# WizFi210_Breakout_Board.net
KiCad netlist of a schematic drawn in EAGLE
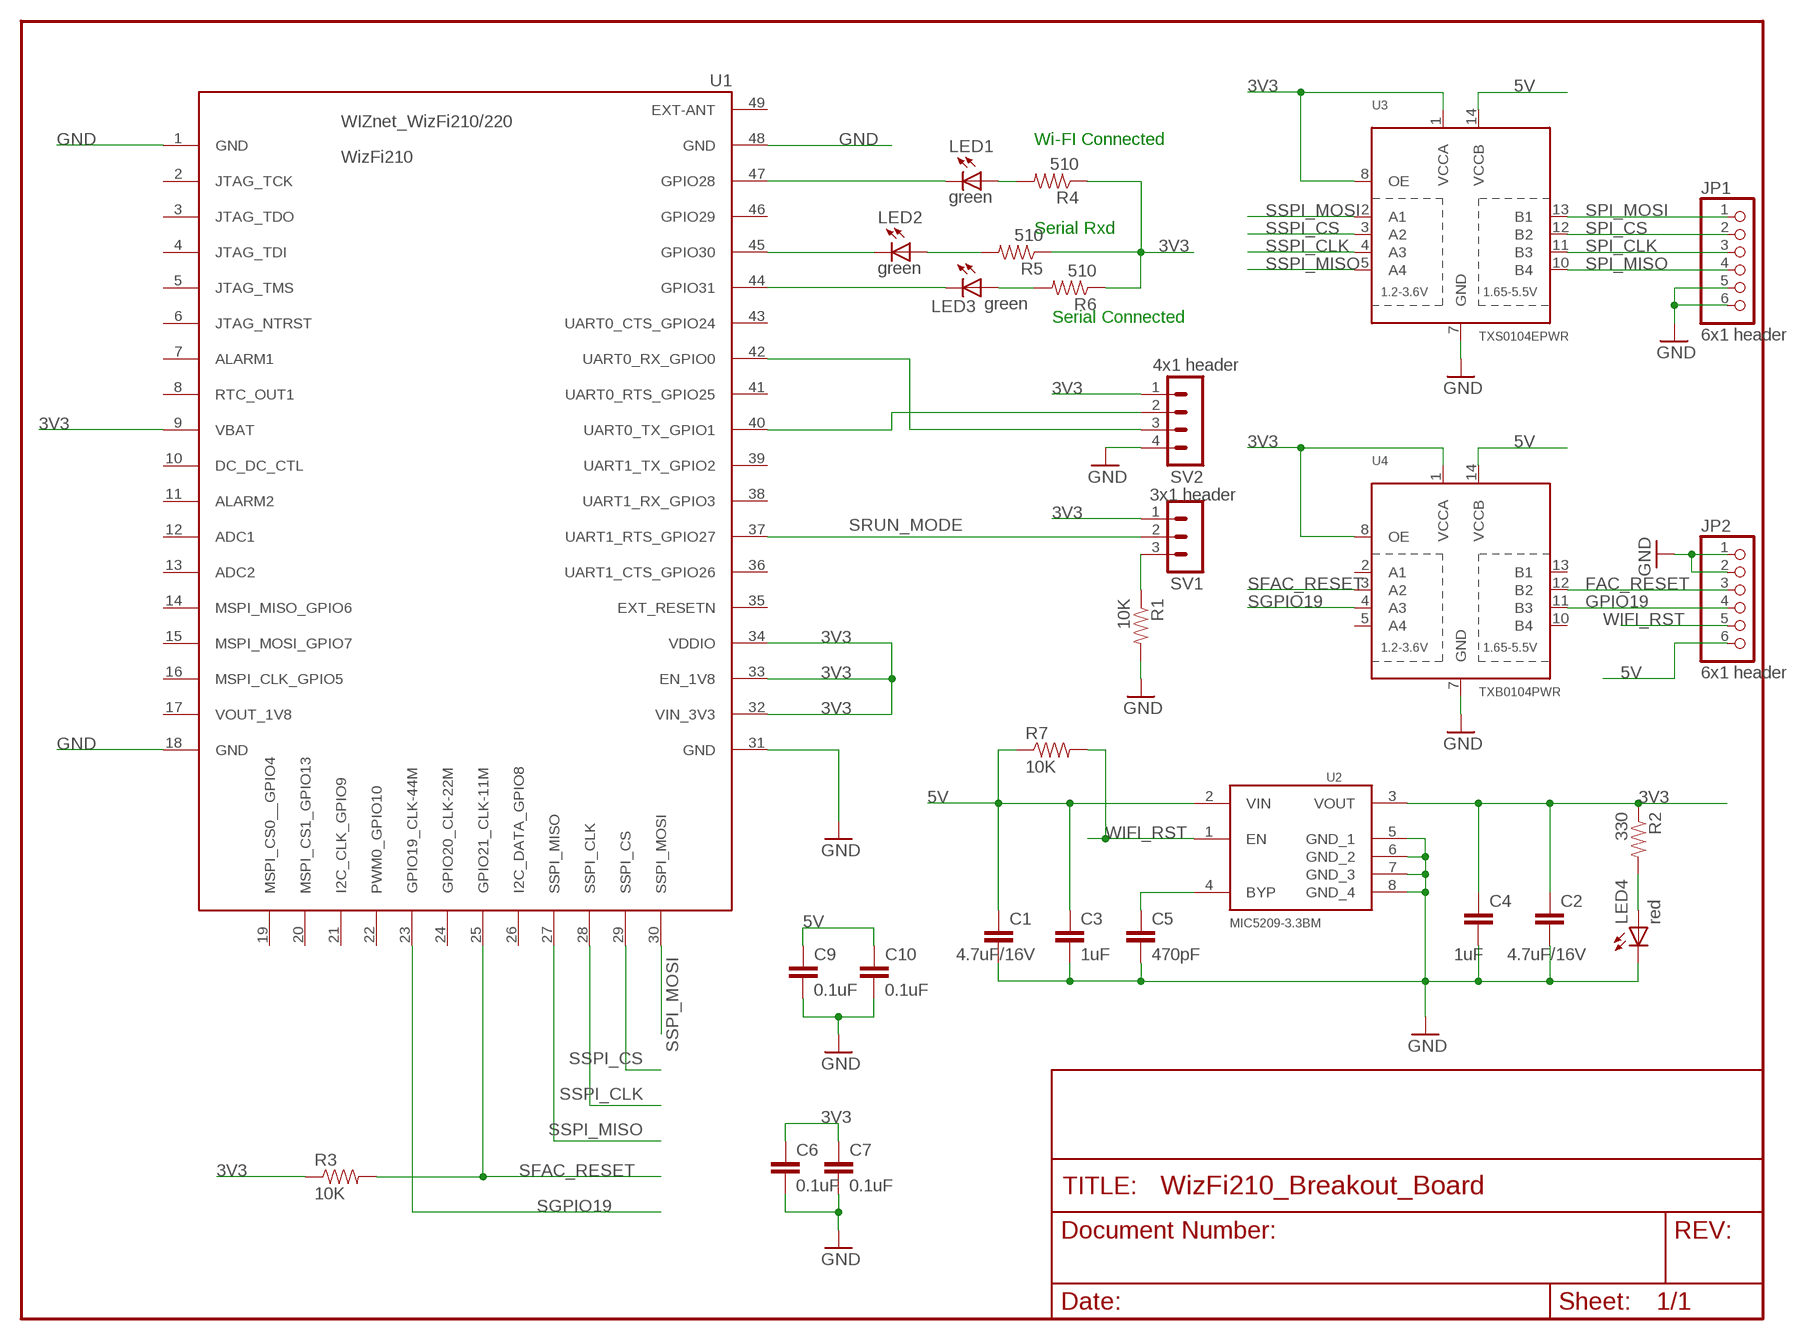
[diagram p0: schematic, sheet 1]

(export (version "E")
  (design (tool "Eeschema 10.0.6"))
  (components
    (comp (ref "C1")
      (value "4.7uF/16V")
      (footprint "eagle-import:C0805")
      (libsource (lib "eagle-import") (part "C-EUC0805"))
    )
    (comp (ref "C2")
      (value "4.7uF/16V")
      (footprint "eagle-import:C0603")
      (libsource (lib "eagle-import") (part "C-EUC0603"))
    )
    (comp (ref "C3")
      (value "1uF")
      (footprint "eagle-import:C0603")
      (libsource (lib "eagle-import") (part "C-EUC0603"))
    )
    (comp (ref "C4")
      (value "1uF")
      (footprint "eagle-import:C0805")
      (libsource (lib "eagle-import") (part "C-EUC0805"))
    )
    (comp (ref "C5")
      (value "470pF")
      (footprint "eagle-import:C0603")
      (libsource (lib "eagle-import") (part "C-EUC0603"))
    )
    (comp (ref "C6")
      (value "0.1uF")
      (footprint "eagle-import:C0603")
      (libsource (lib "eagle-import") (part "C-EUC0603"))
    )
    (comp (ref "C7")
      (value "0.1uF")
      (footprint "eagle-import:C0603")
      (libsource (lib "eagle-import") (part "C-EUC0603"))
    )
    (comp (ref "C9")
      (value "0.1uF")
      (footprint "eagle-import:C0603")
      (libsource (lib "eagle-import") (part "C-EUC0603"))
    )
    (comp (ref "C10")
      (value "0.1uF")
      (footprint "eagle-import:C0603")
      (libsource (lib "eagle-import") (part "C-EUC0603"))
    )
    (comp (ref "JP1")
      (value "6x1 header")
      (footprint "eagle-import:1X06")
      (libsource (lib "eagle-import") (part "PINHD-1X6"))
    )
    (comp (ref "JP2")
      (value "6x1 header")
      (footprint "eagle-import:1X06")
      (libsource (lib "eagle-import") (part "PINHD-1X6"))
    )
    (comp (ref "LED1")
      (value "green")
      (footprint "eagle-import:CHIP-LED0805")
      (libsource (lib "eagle-import") (part "LEDCHIP-LED0805"))
    )
    (comp (ref "LED2")
      (value "green")
      (footprint "eagle-import:CHIP-LED0805")
      (libsource (lib "eagle-import") (part "LEDCHIP-LED0805"))
    )
    (comp (ref "LED3")
      (value "green")
      (footprint "eagle-import:CHIP-LED0805")
      (libsource (lib "eagle-import") (part "LEDCHIP-LED0805"))
    )
    (comp (ref "LED4")
      (value "red")
      (footprint "eagle-import:CHIP-LED0805")
      (libsource (lib "eagle-import") (part "LEDCHIP-LED0805"))
    )
    (comp (ref "R1")
      (value "10K")
      (footprint "eagle-import:0603-RES")
      (libsource (lib "eagle-import") (part "RESISTOR0603-RES"))
    )
    (comp (ref "R2")
      (value "330")
      (footprint "eagle-import:0603-RES")
      (libsource (lib "eagle-import") (part "RESISTOR0603-RES"))
    )
    (comp (ref "R3")
      (value "10K")
      (footprint "eagle-import:0603-RES")
      (libsource (lib "eagle-import") (part "RESISTOR0603-RES"))
    )
    (comp (ref "R4")
      (value "510")
      (footprint "eagle-import:0603-RES")
      (libsource (lib "eagle-import") (part "RESISTOR0603-RES"))
    )
    (comp (ref "R5")
      (value "510")
      (footprint "eagle-import:0603-RES")
      (libsource (lib "eagle-import") (part "RESISTOR0603-RES"))
    )
    (comp (ref "R6")
      (value "510")
      (footprint "eagle-import:0603-RES")
      (libsource (lib "eagle-import") (part "RESISTOR0603-RES"))
    )
    (comp (ref "R7")
      (value "10K")
      (footprint "eagle-import:0603-RES")
      (libsource (lib "eagle-import") (part "RESISTOR0603-RES"))
    )
    (comp (ref "SV1")
      (value "3x1 header")
      (footprint "eagle-import:MA03-1")
      (libsource (lib "eagle-import") (part "MA03-1"))
    )
    (comp (ref "SV2")
      (value "4x1 header")
      (footprint "eagle-import:MA04-1")
      (libsource (lib "eagle-import") (part "MA04-1"))
    )
    (comp (ref "U1")
      (value "WizFi210")
      (footprint "eagle-import:WIZFI210_220")
      (libsource (lib "eagle-import") (part "WIZFI210/220"))
    )
    (comp (ref "U2")
      (value "MIC5209-3.3BM")
      (footprint "eagle-import:SO08")
      (libsource (lib "eagle-import") (part "MIC5209"))
    )
    (comp (ref "U3")
      (value "TXS0104EPWR")
      (footprint "eagle-import:TSSOP14")
      (libsource (lib "eagle-import") (part "TXB0104PWR"))
    )
    (comp (ref "U4")
      (value "TXB0104PWR")
      (footprint "eagle-import:TSSOP14")
      (libsource (lib "eagle-import") (part "TXB0104PWR"))
    )
  )
  (nets
    (net (code "1") (name "/3V3") (class "Default")
      (node (ref "C2") (pin "1") (pinfunction "1_1") (pintype "passive"))
      (node (ref "C4") (pin "1") (pinfunction "1_1") (pintype "passive"))
      (node (ref "C6") (pin "1") (pinfunction "1_1") (pintype "passive"))
      (node (ref "C7") (pin "1") (pinfunction "1_1") (pintype "passive"))
      (node (ref "R2") (pin "1") (pinfunction "1_1") (pintype "passive"))
      (node (ref "R3") (pin "1") (pinfunction "1_1") (pintype "passive"))
      (node (ref "R4") (pin "1") (pinfunction "1_1") (pintype "passive"))
      (node (ref "R5") (pin "1") (pinfunction "1_1") (pintype "passive"))
      (node (ref "R6") (pin "1") (pinfunction "1_1") (pintype "passive"))
      (node (ref "SV1") (pin "1") (pinfunction "1_1") (pintype "passive"))
      (node (ref "SV2") (pin "1") (pinfunction "1_1") (pintype "passive"))
      (node (ref "U1") (pin "32") (pinfunction "VIN_3V3_32") (pintype "power_in"))
      (node (ref "U1") (pin "33") (pinfunction "EN_1V8_33") (pintype "input"))
      (node (ref "U1") (pin "34") (pinfunction "VDDIO_34") (pintype "power_in"))
      (node (ref "U1") (pin "9") (pinfunction "VBAT_9") (pintype "power_in"))
      (node (ref "U2") (pin "3") (pinfunction "VOUT_3") (pintype "output"))
      (node (ref "U3") (pin "1") (pinfunction "VCCA_1") (pintype "bidirectional"))
      (node (ref "U3") (pin "8") (pinfunction "OE_8") (pintype "bidirectional"))
      (node (ref "U4") (pin "1") (pinfunction "VCCA_1") (pintype "bidirectional"))
      (node (ref "U4") (pin "8") (pinfunction "OE_8") (pintype "bidirectional"))
    )
    (net (code "2") (name "/5V") (class "Default")
      (node (ref "C1") (pin "1") (pinfunction "1_1") (pintype "passive"))
      (node (ref "C10") (pin "1") (pinfunction "1_1") (pintype "passive"))
      (node (ref "C3") (pin "1") (pinfunction "1_1") (pintype "passive"))
      (node (ref "C9") (pin "1") (pinfunction "1_1") (pintype "passive"))
      (node (ref "JP2") (pin "6") (pinfunction "6_6") (pintype "passive"))
      (node (ref "R7") (pin "1") (pinfunction "1_1") (pintype "passive"))
      (node (ref "U2") (pin "2") (pinfunction "VIN_2") (pintype "input"))
      (node (ref "U3") (pin "14") (pinfunction "VCCB_14") (pintype "bidirectional"))
      (node (ref "U4") (pin "14") (pinfunction "VCCB_14") (pintype "bidirectional"))
    )
    (net (code "3") (name "/FAC_RESET") (class "Default")
      (node (ref "JP2") (pin "3") (pinfunction "3_3") (pintype "passive"))
      (node (ref "U4") (pin "12") (pinfunction "B2_12") (pintype "bidirectional"))
    )
    (net (code "4") (name "/GPIO19") (class "Default")
      (node (ref "JP2") (pin "4") (pinfunction "4_4") (pintype "passive"))
      (node (ref "U4") (pin "11") (pinfunction "B3_11") (pintype "bidirectional"))
    )
    (net (code "5") (name "/SFAC_RESET") (class "Default")
      (node (ref "R3") (pin "2") (pinfunction "2_2") (pintype "passive"))
      (node (ref "U1") (pin "25") (pinfunction "GPIO21_CLK-11M_25") (pintype "input"))
      (node (ref "U4") (pin "3") (pinfunction "A2_3") (pintype "bidirectional"))
    )
    (net (code "6") (name "/SGPIO19") (class "Default")
      (node (ref "U1") (pin "23") (pinfunction "GPIO19_CLK-44M_23") (pintype "input"))
      (node (ref "U4") (pin "4") (pinfunction "A3_4") (pintype "bidirectional"))
    )
    (net (code "7") (name "/SPI_CLK") (class "Default")
      (node (ref "JP1") (pin "3") (pinfunction "3_3") (pintype "passive"))
      (node (ref "U3") (pin "11") (pinfunction "B3_11") (pintype "bidirectional"))
    )
    (net (code "8") (name "/SPI_CS") (class "Default")
      (node (ref "JP1") (pin "2") (pinfunction "2_2") (pintype "passive"))
      (node (ref "U3") (pin "12") (pinfunction "B2_12") (pintype "bidirectional"))
    )
    (net (code "9") (name "/SPI_MISO") (class "Default")
      (node (ref "JP1") (pin "4") (pinfunction "4_4") (pintype "passive"))
      (node (ref "U3") (pin "10") (pinfunction "B4_10") (pintype "bidirectional"))
    )
    (net (code "10") (name "/SPI_MOSI") (class "Default")
      (node (ref "JP1") (pin "1") (pinfunction "1_1") (pintype "passive"))
      (node (ref "U3") (pin "13") (pinfunction "B1_13") (pintype "bidirectional"))
    )
    (net (code "11") (name "/SRUN_MODE") (class "Default")
      (node (ref "SV1") (pin "2") (pinfunction "2_2") (pintype "passive"))
      (node (ref "U1") (pin "37") (pinfunction "UART1_RTS_GPIO27_37") (pintype "output"))
    )
    (net (code "12") (name "/SSPI_CLK") (class "Default")
      (node (ref "U1") (pin "28") (pinfunction "SSPI_CLK_28") (pintype "input"))
      (node (ref "U3") (pin "4") (pinfunction "A3_4") (pintype "bidirectional"))
    )
    (net (code "13") (name "/SSPI_CS") (class "Default")
      (node (ref "U1") (pin "29") (pinfunction "SSPI_CS_29") (pintype "input"))
      (node (ref "U3") (pin "3") (pinfunction "A2_3") (pintype "bidirectional"))
    )
    (net (code "14") (name "/SSPI_MISO") (class "Default")
      (node (ref "U1") (pin "27") (pinfunction "SSPI_MISO_27") (pintype "output"))
      (node (ref "U3") (pin "5") (pinfunction "A4_5") (pintype "bidirectional"))
    )
    (net (code "15") (name "/SSPI_MOSI") (class "Default")
      (node (ref "U1") (pin "30") (pinfunction "SSPI_MOSI_30") (pintype "input"))
      (node (ref "U3") (pin "2") (pinfunction "A1_2") (pintype "bidirectional"))
    )
    (net (code "16") (name "/WIFI_RST") (class "Default")
      (node (ref "JP2") (pin "5") (pinfunction "5_5") (pintype "passive"))
      (node (ref "R7") (pin "2") (pinfunction "2_2") (pintype "passive"))
      (node (ref "U2") (pin "1") (pinfunction "EN_1") (pintype "input"))
    )
    (net (code "17") (name "GND") (class "Default")
      (node (ref "C1") (pin "2") (pinfunction "2_2") (pintype "passive"))
      (node (ref "C10") (pin "2") (pinfunction "2_2") (pintype "passive"))
      (node (ref "C2") (pin "2") (pinfunction "2_2") (pintype "passive"))
      (node (ref "C3") (pin "2") (pinfunction "2_2") (pintype "passive"))
      (node (ref "C4") (pin "2") (pinfunction "2_2") (pintype "passive"))
      (node (ref "C5") (pin "2") (pinfunction "2_2") (pintype "passive"))
      (node (ref "C6") (pin "2") (pinfunction "2_2") (pintype "passive"))
      (node (ref "C7") (pin "2") (pinfunction "2_2") (pintype "passive"))
      (node (ref "C9") (pin "2") (pinfunction "2_2") (pintype "passive"))
      (node (ref "JP1") (pin "5") (pinfunction "5_5") (pintype "passive"))
      (node (ref "JP1") (pin "6") (pinfunction "6_6") (pintype "passive"))
      (node (ref "JP2") (pin "1") (pinfunction "1_1") (pintype "passive"))
      (node (ref "JP2") (pin "2") (pinfunction "2_2") (pintype "passive"))
      (node (ref "LED4") (pin "C") (pinfunction "C_C") (pintype "passive"))
      (node (ref "R1") (pin "2") (pinfunction "2_2") (pintype "passive"))
      (node (ref "SV2") (pin "4") (pinfunction "4_4") (pintype "passive"))
      (node (ref "U1") (pin "1") (pinfunction "GND_1") (pintype "power_in"))
      (node (ref "U1") (pin "18") (pinfunction "GND_18") (pintype "power_in"))
      (node (ref "U1") (pin "31") (pinfunction "GND_31") (pintype "power_in"))
      (node (ref "U1") (pin "48") (pinfunction "GND_48") (pintype "power_in"))
      (node (ref "U2") (pin "5") (pinfunction "GND_1_5") (pintype "power_in"))
      (node (ref "U2") (pin "6") (pinfunction "GND_2_6") (pintype "power_in"))
      (node (ref "U2") (pin "7") (pinfunction "GND_3_7") (pintype "power_in"))
      (node (ref "U2") (pin "8") (pinfunction "GND_4_8") (pintype "power_in"))
      (node (ref "U3") (pin "7") (pinfunction "GND_7") (pintype "bidirectional"))
      (node (ref "U4") (pin "7") (pinfunction "GND_7") (pintype "bidirectional"))
    )
    (net (code "18") (name "Net-(LED1-PadA)") (class "Default")
      (node (ref "LED1") (pin "A") (pinfunction "A_A") (pintype "passive"))
      (node (ref "R4") (pin "2") (pinfunction "2_2") (pintype "passive"))
    )
    (net (code "19") (name "Net-(LED2-PadA)") (class "Default")
      (node (ref "LED2") (pin "A") (pinfunction "A_A") (pintype "passive"))
      (node (ref "R5") (pin "2") (pinfunction "2_2") (pintype "passive"))
    )
    (net (code "20") (name "Net-(LED3-PadA)") (class "Default")
      (node (ref "LED3") (pin "A") (pinfunction "A_A") (pintype "passive"))
      (node (ref "R6") (pin "2") (pinfunction "2_2") (pintype "passive"))
    )
    (net (code "21") (name "Net-(LED4-PadA)") (class "Default")
      (node (ref "LED4") (pin "A") (pinfunction "A_A") (pintype "passive"))
      (node (ref "R2") (pin "2") (pinfunction "2_2") (pintype "passive"))
    )
    (net (code "22") (name "Net-(R1-Pad1)") (class "Default")
      (node (ref "R1") (pin "1") (pinfunction "1_1") (pintype "passive"))
      (node (ref "SV1") (pin "3") (pinfunction "3_3") (pintype "passive"))
    )
    (net (code "23") (name "Net-(U1-GPIO28)") (class "Default")
      (node (ref "LED1") (pin "C") (pinfunction "C_C") (pintype "passive"))
      (node (ref "U1") (pin "47") (pinfunction "GPIO28_47") (pintype "bidirectional"))
    )
    (net (code "24") (name "Net-(U1-GPIO30)") (class "Default")
      (node (ref "LED2") (pin "C") (pinfunction "C_C") (pintype "passive"))
      (node (ref "U1") (pin "45") (pinfunction "GPIO30_45") (pintype "bidirectional"))
    )
    (net (code "25") (name "Net-(U1-GPIO31)") (class "Default")
      (node (ref "LED3") (pin "C") (pinfunction "C_C") (pintype "passive"))
      (node (ref "U1") (pin "44") (pinfunction "GPIO31_44") (pintype "bidirectional"))
    )
    (net (code "26") (name "Net-(U1-UART0_RX_GPIO0)") (class "Default")
      (node (ref "SV2") (pin "3") (pinfunction "3_3") (pintype "passive"))
      (node (ref "U1") (pin "42") (pinfunction "UART0_RX_GPIO0_42") (pintype "input"))
    )
    (net (code "27") (name "Net-(U1-UART0_TX_GPIO1)") (class "Default")
      (node (ref "SV2") (pin "2") (pinfunction "2_2") (pintype "passive"))
      (node (ref "U1") (pin "40") (pinfunction "UART0_TX_GPIO1_40") (pintype "output"))
    )
    (net (code "28") (name "Net-(U2-BYP)") (class "Default")
      (node (ref "C5") (pin "1") (pinfunction "1_1") (pintype "passive"))
      (node (ref "U2") (pin "4") (pinfunction "BYP_4") (pintype "input"))
    )
    (net (code "29") (name "unconnected-(U1-ADC1-Pad12)") (class "Default")
      (node (ref "U1") (pin "12") (pinfunction "ADC1_12") (pintype "input"))
    )
    (net (code "30") (name "unconnected-(U1-ADC2-Pad13)") (class "Default")
      (node (ref "U1") (pin "13") (pinfunction "ADC2_13") (pintype "input"))
    )
    (net (code "31") (name "unconnected-(U1-ALARM1-Pad7)") (class "Default")
      (node (ref "U1") (pin "7") (pinfunction "ALARM1_7") (pintype "input"))
    )
    (net (code "32") (name "unconnected-(U1-ALARM2-Pad11)") (class "Default")
      (node (ref "U1") (pin "11") (pinfunction "ALARM2_11") (pintype "input"))
    )
    (net (code "33") (name "unconnected-(U1-DC_DC_CTL-Pad10)") (class "Default")
      (node (ref "U1") (pin "10") (pinfunction "DC_DC_CTL_10") (pintype "output"))
    )
    (net (code "34") (name "unconnected-(U1-EXT-ANT-Pad49)") (class "Default")
      (node (ref "U1") (pin "49") (pinfunction "EXT-ANT_49") (pintype "bidirectional"))
    )
    (net (code "35") (name "unconnected-(U1-EXT_RESETN-Pad35)") (class "Default")
      (node (ref "U1") (pin "35") (pinfunction "EXT_RESETN_35") (pintype "bidirectional"))
    )
    (net (code "36") (name "unconnected-(U1-GPIO20_CLK-22M-Pad24)") (class "Default")
      (node (ref "U1") (pin "24") (pinfunction "GPIO20_CLK-22M_24") (pintype "input"))
    )
    (net (code "37") (name "unconnected-(U1-GPIO29-Pad46)") (class "Default")
      (node (ref "U1") (pin "46") (pinfunction "GPIO29_46") (pintype "bidirectional"))
    )
    (net (code "38") (name "unconnected-(U1-I2C_CLK_GPIO9-Pad21)") (class "Default")
      (node (ref "U1") (pin "21") (pinfunction "I2C_CLK_GPIO9_21") (pintype "bidirectional"))
    )
    (net (code "39") (name "unconnected-(U1-I2C_DATA_GPIO8-Pad26)") (class "Default")
      (node (ref "U1") (pin "26") (pinfunction "I2C_DATA_GPIO8_26") (pintype "bidirectional"))
    )
    (net (code "40") (name "unconnected-(U1-JTAG_NTRST-Pad6)") (class "Default")
      (node (ref "U1") (pin "6") (pinfunction "JTAG_NTRST_6") (pintype "input"))
    )
    (net (code "41") (name "unconnected-(U1-JTAG_TCK-Pad2)") (class "Default")
      (node (ref "U1") (pin "2") (pinfunction "JTAG_TCK_2") (pintype "input"))
    )
    (net (code "42") (name "unconnected-(U1-JTAG_TDI-Pad4)") (class "Default")
      (node (ref "U1") (pin "4") (pinfunction "JTAG_TDI_4") (pintype "input"))
    )
    (net (code "43") (name "unconnected-(U1-JTAG_TDO-Pad3)") (class "Default")
      (node (ref "U1") (pin "3") (pinfunction "JTAG_TDO_3") (pintype "output"))
    )
    (net (code "44") (name "unconnected-(U1-JTAG_TMS-Pad5)") (class "Default")
      (node (ref "U1") (pin "5") (pinfunction "JTAG_TMS_5") (pintype "input"))
    )
    (net (code "45") (name "unconnected-(U1-MSPI_CLK_GPIO5-Pad16)") (class "Default")
      (node (ref "U1") (pin "16") (pinfunction "MSPI_CLK_GPIO5_16") (pintype "bidirectional"))
    )
    (net (code "46") (name "unconnected-(U1-MSPI_CS0__GPIO4-Pad19)") (class "Default")
      (node (ref "U1") (pin "19") (pinfunction "MSPI_CS0__GPIO4_19") (pintype "output"))
    )
    (net (code "47") (name "unconnected-(U1-MSPI_CS1_GPIO13-Pad20)") (class "Default")
      (node (ref "U1") (pin "20") (pinfunction "MSPI_CS1_GPIO13_20") (pintype "output"))
    )
    (net (code "48") (name "unconnected-(U1-MSPI_MISO_GPIO6-Pad14)") (class "Default")
      (node (ref "U1") (pin "14") (pinfunction "MSPI_MISO_GPIO6_14") (pintype "input"))
    )
    (net (code "49") (name "unconnected-(U1-MSPI_MOSI_GPIO7-Pad15)") (class "Default")
      (node (ref "U1") (pin "15") (pinfunction "MSPI_MOSI_GPIO7_15") (pintype "output"))
    )
    (net (code "50") (name "unconnected-(U1-PWM0_GPIO10-Pad22)") (class "Default")
      (node (ref "U1") (pin "22") (pinfunction "PWM0_GPIO10_22") (pintype "output"))
    )
    (net (code "51") (name "unconnected-(U1-RTC_OUT1-Pad8)") (class "Default")
      (node (ref "U1") (pin "8") (pinfunction "RTC_OUT1_8") (pintype "output"))
    )
    (net (code "52") (name "unconnected-(U1-UART0_CTS_GPIO24-Pad43)") (class "Default")
      (node (ref "U1") (pin "43") (pinfunction "UART0_CTS_GPIO24_43") (pintype "input"))
    )
    (net (code "53") (name "unconnected-(U1-UART0_RTS_GPIO25-Pad41)") (class "Default")
      (node (ref "U1") (pin "41") (pinfunction "UART0_RTS_GPIO25_41") (pintype "output"))
    )
    (net (code "54") (name "unconnected-(U1-UART1_CTS_GPIO26-Pad36)") (class "Default")
      (node (ref "U1") (pin "36") (pinfunction "UART1_CTS_GPIO26_36") (pintype "input"))
    )
    (net (code "55") (name "unconnected-(U1-UART1_RX_GPIO3-Pad38)") (class "Default")
      (node (ref "U1") (pin "38") (pinfunction "UART1_RX_GPIO3_38") (pintype "input"))
    )
    (net (code "56") (name "unconnected-(U1-UART1_TX_GPIO2-Pad39)") (class "Default")
      (node (ref "U1") (pin "39") (pinfunction "UART1_TX_GPIO2_39") (pintype "output"))
    )
    (net (code "57") (name "unconnected-(U1-VOUT_1V8-Pad17)") (class "Default")
      (node (ref "U1") (pin "17") (pinfunction "VOUT_1V8_17") (pintype "bidirectional"))
    )
    (net (code "58") (name "unconnected-(U4-A1-Pad2)") (class "Default")
      (node (ref "U4") (pin "2") (pinfunction "A1_2") (pintype "bidirectional"))
    )
    (net (code "59") (name "unconnected-(U4-A4-Pad5)") (class "Default")
      (node (ref "U4") (pin "5") (pinfunction "A4_5") (pintype "bidirectional"))
    )
    (net (code "60") (name "unconnected-(U4-B1-Pad13)") (class "Default")
      (node (ref "U4") (pin "13") (pinfunction "B1_13") (pintype "bidirectional"))
    )
    (net (code "61") (name "unconnected-(U4-B4-Pad10)") (class "Default")
      (node (ref "U4") (pin "10") (pinfunction "B4_10") (pintype "bidirectional"))
    )
  )
)
